# EspLight.net
KiCad netlist of a schematic drawn in EAGLE
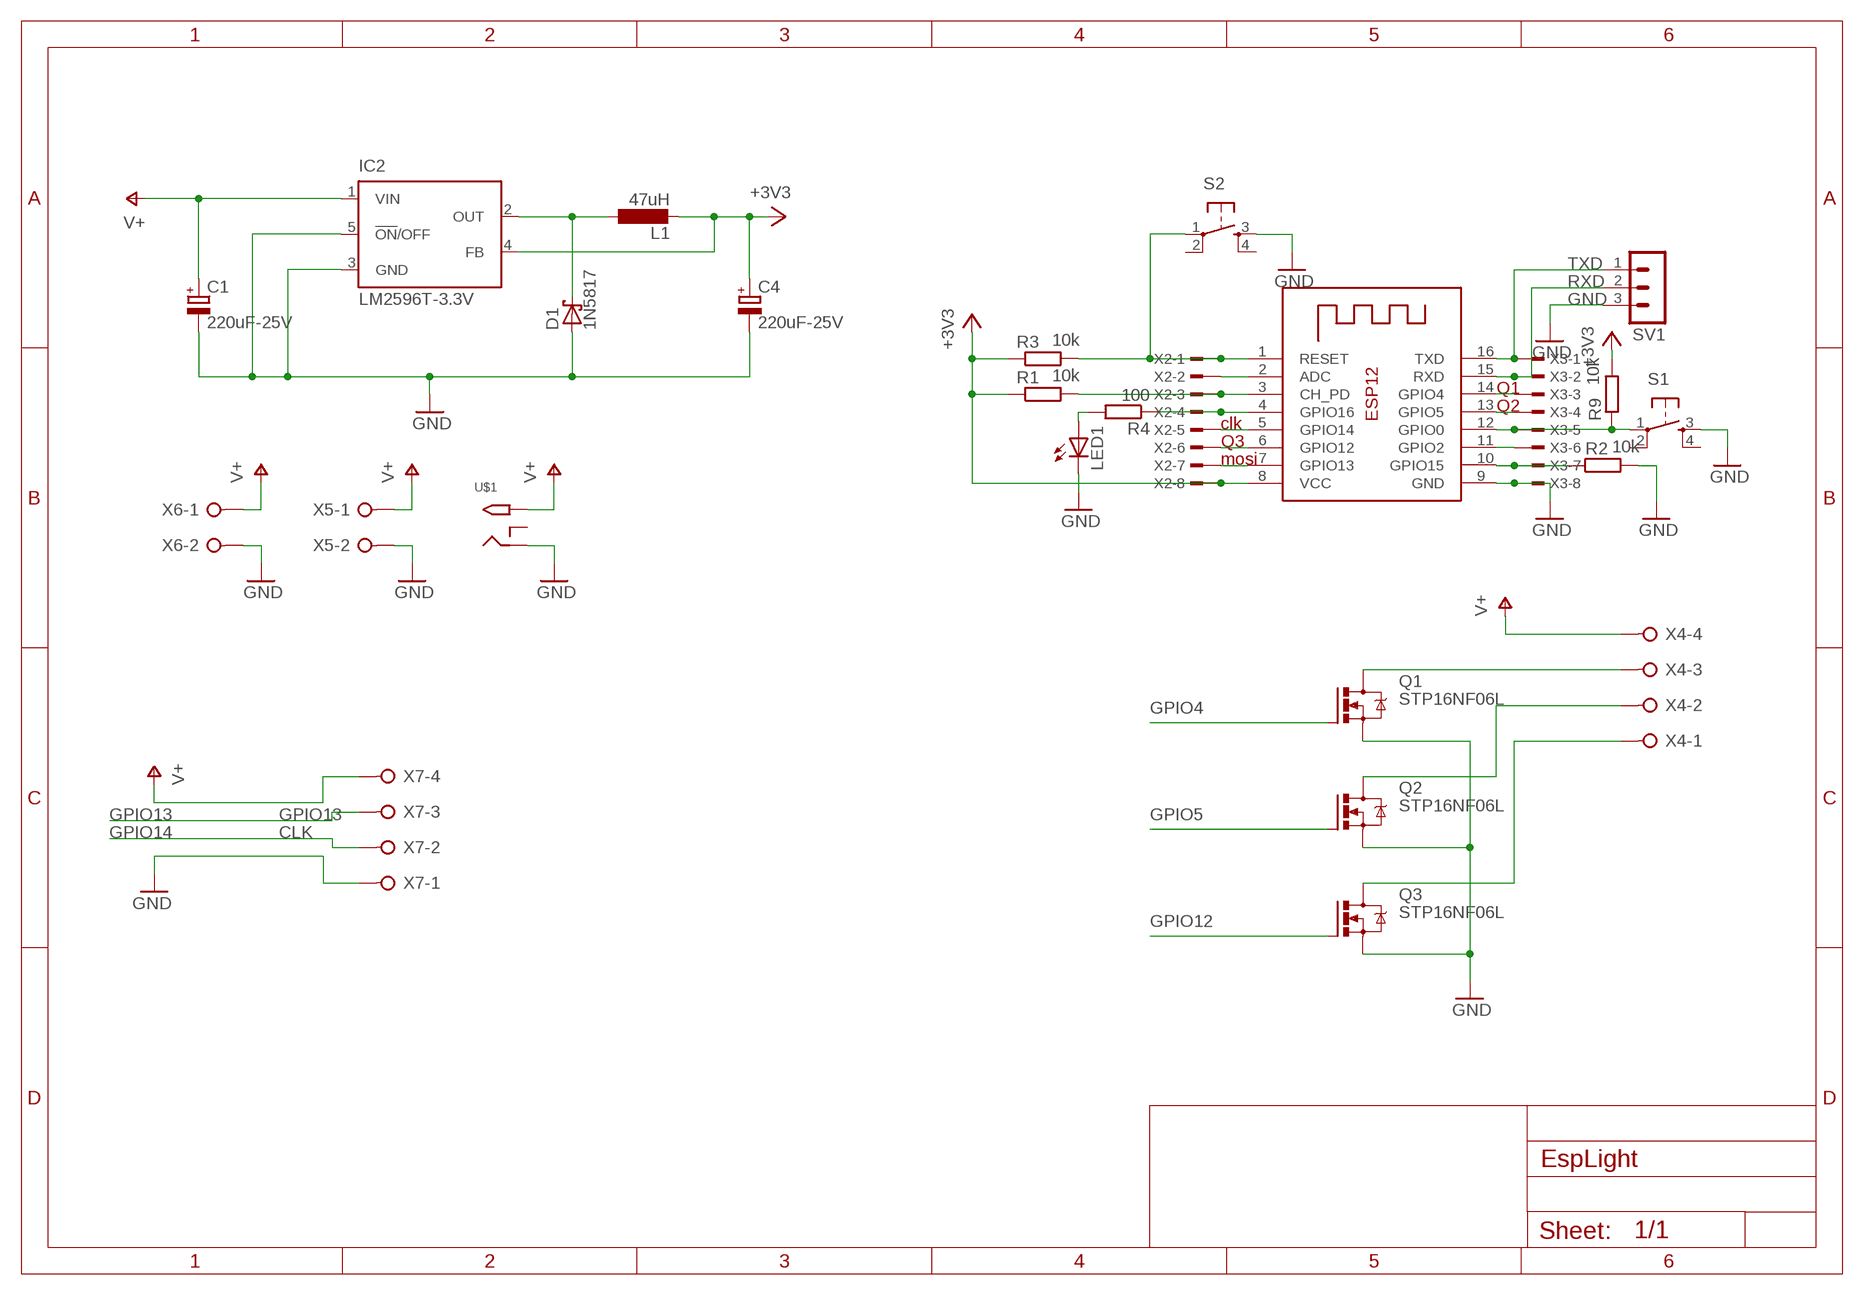
[diagram p0: schematic, sheet 1]

(export (version "E")
  (design (tool "Eeschema 10.0.6"))
  (components
    (comp (ref "C1")
      (value "220uF-25V")
      (footprint "eagle-import:E2,5-7")
      (libsource (lib "eagle-import") (part "CPOL-EUE2.5-7"))
    )
    (comp (ref "C4")
      (value "220uF-25V")
      (footprint "eagle-import:E2,5-7")
      (libsource (lib "eagle-import") (part "CPOL-EUE2.5-7"))
    )
    (comp (ref "D1")
      (value "1N5817")
      (footprint "eagle-import:DO41-7.6")
      (libsource (lib "eagle-import") (part "1N5817-B"))
    )
    (comp (ref "IC2")
      (value "LM2596T-3.3V")
      (footprint "eagle-import:T05D")
      (fields (field (name "MPN") "LM2596T-ADJ/LF02"))
      (libsource (lib "eagle-import") (part "LM2596T"))
    )
    (comp (ref "L1")
      (value "47uH")
      (footprint "eagle-import:6000-XXXX-RC")
      (libsource (lib "eagle-import") (part "L-EU6000-XXX-RC"))
    )
    (comp (ref "LED1")
      (value "LED5MM")
      (footprint "eagle-import:LED5MM")
      (libsource (lib "eagle-import") (part "LED5MM"))
    )
    (comp (ref "Q1")
      (value "STP16NF06L")
      (footprint "eagle-import:TO220BV")
      (libsource (lib "eagle-import") (part "IRF540"))
    )
    (comp (ref "Q2")
      (value "STP16NF06L")
      (footprint "eagle-import:TO220BV")
      (libsource (lib "eagle-import") (part "IRF540"))
    )
    (comp (ref "Q3")
      (value "STP16NF06L")
      (footprint "eagle-import:TO220BV")
      (libsource (lib "eagle-import") (part "IRF540"))
    )
    (comp (ref "R1")
      (value "10k")
      (footprint "eagle-import:0207_10")
      (libsource (lib "eagle-import") (part "R-EU_0207/10"))
    )
    (comp (ref "R2")
      (value "10k")
      (footprint "eagle-import:0207_10")
      (libsource (lib "eagle-import") (part "R-EU_0207/10"))
    )
    (comp (ref "R3")
      (value "10k")
      (footprint "eagle-import:0207_10")
      (libsource (lib "eagle-import") (part "R-EU_0207/10"))
    )
    (comp (ref "R4")
      (value "100")
      (footprint "eagle-import:0207_10")
      (libsource (lib "eagle-import") (part "R-EU_0207/10"))
    )
    (comp (ref "R9")
      (value "10k")
      (footprint "eagle-import:0207_10")
      (libsource (lib "eagle-import") (part "R-EU_0207/10"))
    )
    (comp (ref "S1")
      (value "TAC_SWITCHPTH")
      (footprint "eagle-import:TACTILE-PTH")
      (libsource (lib "eagle-import") (part "TAC_SWITCHPTH"))
    )
    (comp (ref "S2")
      (value "TAC_SWITCHPTH")
      (footprint "eagle-import:TACTILE-PTH")
      (libsource (lib "eagle-import") (part "TAC_SWITCHPTH"))
    )
    (comp (ref "SV1")
      (value "MA03-1")
      (footprint "eagle-import:MA03-1")
      (libsource (lib "eagle-import") (part "MA03-1"))
    )
    (comp (ref "U$1")
      (value "2.1MMJACKTHM")
      (footprint "eagle-import:PJ-102A")
      (libsource (lib "eagle-import") (part "2.1MMJACKTHM"))
    )
    (comp (ref "X1")
      (value "ESP-12")
      (footprint "eagle-import:ESP-12")
      (libsource (lib "eagle-import") (part "ESP-12"))
    )
    (comp (ref "X2")
      (value "TSW-108-02-S-S")
      (footprint "eagle-import:TSW-108-02-S-S")
      (libsource (lib "eagle-import") (part "TSW-108-02-S-S"))
    )
    (comp (ref "X3")
      (value "TSW-108-02-S-S")
      (footprint "eagle-import:TSW-108-02-S-S")
      (libsource (lib "eagle-import") (part "TSW-108-02-S-S"))
    )
    (comp (ref "X4")
      (value "W237-04P")
      (footprint "eagle-import:W237-4P")
      (libsource (lib "eagle-import") (part "W237-04P"))
    )
    (comp (ref "X5")
      (value "W237-02P")
      (footprint "eagle-import:W237-132")
      (libsource (lib "eagle-import") (part "W237-02P"))
    )
    (comp (ref "X6")
      (value "W237-02P")
      (footprint "eagle-import:W237-132")
      (libsource (lib "eagle-import") (part "W237-02P"))
    )
    (comp (ref "X7")
      (value "W237-04P")
      (footprint "eagle-import:W237-4P")
      (libsource (lib "eagle-import") (part "W237-04P"))
    )
  )
  (nets
    (net (code "1") (name "+3V3") (class "Default")
      (node (ref "C4") (pin "+") (pinfunction "+_+") (pintype "passive"))
      (node (ref "IC2") (pin "4") (pinfunction "FB_4") (pintype "input"))
      (node (ref "L1") (pin "2") (pinfunction "2_2") (pintype "passive"))
      (node (ref "R1") (pin "1") (pinfunction "1_1") (pintype "passive"))
      (node (ref "R3") (pin "1") (pinfunction "1_1") (pintype "passive"))
      (node (ref "R9") (pin "2") (pinfunction "2_2") (pintype "passive"))
      (node (ref "X1") (pin "8") (pinfunction "VCC_8") (pintype "power_in"))
      (node (ref "X2") (pin "8") (pinfunction "1_8") (pintype "passive"))
    )
    (net (code "2") (name "/GPIO4") (class "Default")
      (node (ref "Q1") (pin "G") (pinfunction "G_G") (pintype "passive"))
      (node (ref "X1") (pin "14") (pinfunction "GPIO4_14") (pintype "bidirectional"))
      (node (ref "X3") (pin "3") (pinfunction "1_3") (pintype "passive"))
    )
    (net (code "3") (name "/GPIO5") (class "Default")
      (node (ref "Q2") (pin "G") (pinfunction "G_G") (pintype "passive"))
      (node (ref "X1") (pin "13") (pinfunction "GPIO5_13") (pintype "bidirectional"))
      (node (ref "X3") (pin "4") (pinfunction "1_4") (pintype "passive"))
    )
    (net (code "4") (name "/GPIO12") (class "Default")
      (node (ref "Q3") (pin "G") (pinfunction "G_G") (pintype "passive"))
      (node (ref "X1") (pin "6") (pinfunction "GPIO12_6") (pintype "bidirectional"))
      (node (ref "X2") (pin "6") (pinfunction "1_6") (pintype "passive"))
    )
    (net (code "5") (name "/GPIO13") (class "Default")
      (node (ref "X1") (pin "7") (pinfunction "GPIO13_7") (pintype "bidirectional"))
      (node (ref "X2") (pin "7") (pinfunction "1_7") (pintype "passive"))
      (node (ref "X7") (pin "3") (pinfunction "KL_3") (pintype "passive"))
    )
    (net (code "6") (name "/GPIO14") (class "Default")
      (node (ref "X1") (pin "5") (pinfunction "GPIO14_5") (pintype "bidirectional"))
      (node (ref "X2") (pin "5") (pinfunction "1_5") (pintype "passive"))
      (node (ref "X7") (pin "2") (pinfunction "KL_2") (pintype "passive"))
    )
    (net (code "7") (name "/RXD") (class "Default")
      (node (ref "SV1") (pin "2") (pinfunction "2_2") (pintype "passive"))
      (node (ref "X1") (pin "15") (pinfunction "RXD_15") (pintype "input"))
      (node (ref "X3") (pin "2") (pinfunction "1_2") (pintype "passive"))
    )
    (net (code "8") (name "/TXD") (class "Default")
      (node (ref "SV1") (pin "1") (pinfunction "1_1") (pintype "passive"))
      (node (ref "X1") (pin "16") (pinfunction "TXD_16") (pintype "output"))
      (node (ref "X3") (pin "1") (pinfunction "1_1") (pintype "passive"))
    )
    (net (code "9") (name "GND") (class "Default")
      (node (ref "C1") (pin "-") (pinfunction "-_-") (pintype "passive"))
      (node (ref "C4") (pin "-") (pinfunction "-_-") (pintype "passive"))
      (node (ref "D1") (pin "A") (pinfunction "A_A") (pintype "passive"))
      (node (ref "IC2") (pin "3") (pinfunction "GND_3") (pintype "power_in"))
      (node (ref "IC2") (pin "5") (pinfunction "~{ON}/OFF_5") (pintype "input"))
      (node (ref "LED1") (pin "K") (pinfunction "C_K") (pintype "passive"))
      (node (ref "Q1") (pin "S") (pinfunction "S_S") (pintype "passive"))
      (node (ref "Q2") (pin "S") (pinfunction "S_S") (pintype "passive"))
      (node (ref "Q3") (pin "S") (pinfunction "S_S") (pintype "passive"))
      (node (ref "R2") (pin "2") (pinfunction "2_2") (pintype "passive"))
      (node (ref "S1") (pin "3") (pinfunction "3_3") (pintype "passive"))
      (node (ref "S2") (pin "3") (pinfunction "3_3") (pintype "passive"))
      (node (ref "SV1") (pin "3") (pinfunction "3_3") (pintype "passive"))
      (node (ref "U$1") (pin "RING") (pinfunction "RING_RING") (pintype "bidirectional"))
      (node (ref "X1") (pin "9") (pinfunction "GND_9") (pintype "power_in"))
      (node (ref "X3") (pin "8") (pinfunction "1_8") (pintype "passive"))
      (node (ref "X5") (pin "2") (pinfunction "KL_2") (pintype "passive"))
      (node (ref "X6") (pin "2") (pinfunction "KL_2") (pintype "passive"))
      (node (ref "X7") (pin "1") (pinfunction "KL_1") (pintype "passive"))
    )
    (net (code "10") (name "Net-(IC2-OUT)") (class "Default")
      (node (ref "D1") (pin "C") (pinfunction "C_C") (pintype "passive"))
      (node (ref "IC2") (pin "2") (pinfunction "OUT_2") (pintype "output"))
      (node (ref "L1") (pin "1") (pinfunction "1_1") (pintype "passive"))
    )
    (net (code "11") (name "Net-(LED1-PadA)") (class "Default")
      (node (ref "LED1") (pin "A") (pinfunction "A_A") (pintype "passive"))
      (node (ref "R4") (pin "2") (pinfunction "2_2") (pintype "passive"))
    )
    (net (code "12") (name "Net-(X1-ADC)") (class "Default")
      (node (ref "X1") (pin "2") (pinfunction "ADC_2") (pintype "passive"))
      (node (ref "X2") (pin "2") (pinfunction "1_2") (pintype "passive"))
    )
    (net (code "13") (name "Net-(X1-CH_PD)") (class "Default")
      (node (ref "R1") (pin "2") (pinfunction "2_2") (pintype "passive"))
      (node (ref "X1") (pin "3") (pinfunction "CH_PD_3") (pintype "input"))
      (node (ref "X2") (pin "3") (pinfunction "1_3") (pintype "passive"))
    )
    (net (code "14") (name "Net-(X1-GPIO0)") (class "Default")
      (node (ref "R9") (pin "1") (pinfunction "1_1") (pintype "passive"))
      (node (ref "S1") (pin "1") (pinfunction "1_1") (pintype "passive"))
      (node (ref "X1") (pin "12") (pinfunction "GPIO0_12") (pintype "bidirectional"))
      (node (ref "X3") (pin "5") (pinfunction "1_5") (pintype "passive"))
    )
    (net (code "15") (name "Net-(X1-GPIO2)") (class "Default")
      (node (ref "X1") (pin "11") (pinfunction "GPIO2_11") (pintype "bidirectional"))
      (node (ref "X3") (pin "6") (pinfunction "1_6") (pintype "passive"))
    )
    (net (code "16") (name "Net-(X1-GPIO15)") (class "Default")
      (node (ref "R2") (pin "1") (pinfunction "1_1") (pintype "passive"))
      (node (ref "X1") (pin "10") (pinfunction "GPIO15_10") (pintype "bidirectional"))
      (node (ref "X3") (pin "7") (pinfunction "1_7") (pintype "passive"))
    )
    (net (code "17") (name "Net-(X1-GPIO16)") (class "Default")
      (node (ref "R4") (pin "1") (pinfunction "1_1") (pintype "passive"))
      (node (ref "X1") (pin "4") (pinfunction "GPIO16_4") (pintype "bidirectional"))
      (node (ref "X2") (pin "4") (pinfunction "1_4") (pintype "passive"))
    )
    (net (code "18") (name "Net-(X1-RESET)") (class "Default")
      (node (ref "R3") (pin "2") (pinfunction "2_2") (pintype "passive"))
      (node (ref "S2") (pin "1") (pinfunction "1_1") (pintype "passive"))
      (node (ref "X1") (pin "1") (pinfunction "RESET_1") (pintype "input"))
      (node (ref "X2") (pin "1") (pinfunction "1_1") (pintype "passive"))
    )
    (net (code "19") (name "Net-(X4A-KL)") (class "Default")
      (node (ref "Q3") (pin "D") (pinfunction "D_D") (pintype "passive"))
      (node (ref "X4") (pin "1") (pinfunction "KL_1") (pintype "passive"))
    )
    (net (code "20") (name "Net-(X4B-KL)") (class "Default")
      (node (ref "Q2") (pin "D") (pinfunction "D_D") (pintype "passive"))
      (node (ref "X4") (pin "2") (pinfunction "KL_2") (pintype "passive"))
    )
    (net (code "21") (name "Net-(X4C-KL)") (class "Default")
      (node (ref "Q1") (pin "D") (pinfunction "D_D") (pintype "passive"))
      (node (ref "X4") (pin "3") (pinfunction "KL_3") (pintype "passive"))
    )
    (net (code "22") (name "V+") (class "Default")
      (node (ref "C1") (pin "+") (pinfunction "+_+") (pintype "passive"))
      (node (ref "IC2") (pin "1") (pinfunction "VIN_1") (pintype "input"))
      (node (ref "U$1") (pin "TIP") (pinfunction "TIP_TIP") (pintype "bidirectional"))
      (node (ref "X4") (pin "4") (pinfunction "KL_4") (pintype "passive"))
      (node (ref "X5") (pin "1") (pinfunction "KL_1") (pintype "passive"))
      (node (ref "X6") (pin "1") (pinfunction "KL_1") (pintype "passive"))
      (node (ref "X7") (pin "4") (pinfunction "KL_4") (pintype "passive"))
    )
    (net (code "23") (name "unconnected-(S1-Pad2)") (class "Default")
      (node (ref "S1") (pin "2") (pinfunction "2_2") (pintype "passive"))
    )
    (net (code "24") (name "unconnected-(S1-Pad4)") (class "Default")
      (node (ref "S1") (pin "4") (pinfunction "4_4") (pintype "passive"))
    )
    (net (code "25") (name "unconnected-(S2-Pad2)") (class "Default")
      (node (ref "S2") (pin "2") (pinfunction "2_2") (pintype "passive"))
    )
    (net (code "26") (name "unconnected-(S2-Pad4)") (class "Default")
      (node (ref "S2") (pin "4") (pinfunction "4_4") (pintype "passive"))
    )
    (net (code "27") (name "unconnected-(U$1-PadRING_SW)") (class "Default")
      (node (ref "U$1") (pin "RING_SW") (pinfunction "RING_SW_RING_SW") (pintype "bidirectional"))
    )
  )
)
